# Sheet1.net
KiCad netlist of a schematic drawn in Altium Designer
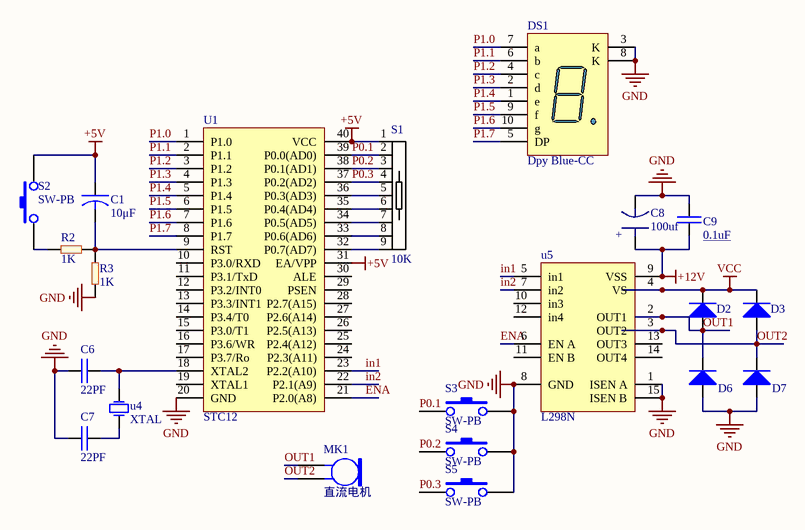
[diagram p0: Sheet1.SchDoc]

(export (version "E")
  (design (tool "Eeschema 10.0.6"))
  (components
    (comp (ref "C1")
      (value "10μF")
      (footprint "电解电容")
      (description "Capacitor")
      (libsource (lib "考核") (part "CAPACITOR"))
    )
    (comp (ref "C6") (value "22PF") (footprint "瓷片电容") (libsource (lib "考核") (part "瓷片电容")))
    (comp (ref "C7") (value "22PF") (footprint "瓷片电容") (libsource (lib "考核") (part "瓷片电容")))
    (comp (ref "C8") (value "100uf") (footprint "电解电容") (libsource (lib "考核") (part "电解电容")))
    (comp (ref "C9") (value "0.1uF") (footprint "瓷片电容") (libsource (lib "考核") (part "瓷片电容_1")))
    (comp (ref "D2")
      (value "1N4007")
      (footprint "二极管 直插")
      (fields (field (name "PUBLISHER") "Altium Limited"))
      (libsource (lib "考核") (part "1N4007"))
    )
    (comp (ref "D3")
      (value "1N4007")
      (footprint "二极管 直插")
      (fields (field (name "PUBLISHER") "Altium Limited"))
      (libsource (lib "考核") (part "1N4007"))
    )
    (comp (ref "D6")
      (value "1N4007")
      (footprint "二极管 直插")
      (fields (field (name "PUBLISHER") "Altium Limited"))
      (libsource (lib "考核") (part "1N4007"))
    )
    (comp (ref "D7")
      (value "1N4007")
      (footprint "二极管 直插")
      (fields (field (name "PUBLISHER") "Altium Limited"))
      (libsource (lib "考核") (part "1N4007"))
    )
    (comp (ref "DS1")
      (value "Dpy Blue-CC")
      (footprint "LEDDIP-10/C15.24RHD")
      (description "14.2 mm General Purpose Blue 7-Segment Display: CC, RH DP, Gray Surface")
      (fields (field (name "PUBLISHER") "Altium Limited"))
      (libsource (lib "考核") (part "Dpy Blue-CC"))
    )
    (comp (ref "MK1")
      (value "直流电机")
      (footprint "PIN2")
      (description "Microphone")
      (fields (field (name "PUBLISHER") "Altium Limited"))
      (libsource (lib "考核") (part "Mic2"))
    )
    (comp (ref "R2") (value "1K") (footprint "电阻") (libsource (lib "") (part "R_1")))
    (comp (ref "R3") (value "1K") (footprint "电阻") (libsource (lib "考核") (part "R")))
    (comp (ref "S1") (value "10K") (footprint "SIP9") (libsource (lib "考核") (part "RES-9")))
    (comp (ref "S2") (value "SW-PB") (footprint "ANJIAN") (libsource (lib "考核") (part "SW-PB")))
    (comp (ref "S3") (value "SW-PB") (footprint "ANJIAN") (libsource (lib "考核") (part "SW-PB")))
    (comp (ref "S4") (value "SW-PB") (footprint "ANJIAN") (libsource (lib "考核") (part "SW-PB")))
    (comp (ref "S5") (value "SW-PB") (footprint "ANJIAN") (libsource (lib "考核") (part "SW-PB")))
    (comp (ref "U1") (value "STC12") (footprint "STC52") (libsource (lib "考核") (part "12单片机")))
    (comp (ref "u4") (value "XTAL") (footprint "晶振.") (libsource (lib "考核") (part "XTAL")))
    (comp (ref "u5") (value "L298N") (footprint "L298N") (libsource (lib "考核") (part "L298N")))
  )
  (nets
    (net (code "1") (name "+5V") (class "Default")
      (node (ref "C1") (pin "1") (pinfunction "1_1") (pintype "passive"))
      (node (ref "S1") (pin "1") (pinfunction "1_1") (pintype "open_collector"))
      (node (ref "S2") (pin "2") (pinfunction "2_2") (pintype "passive"))
      (node (ref "U1") (pin "31") (pinfunction "EA/VPP_31") (pintype "passive"))
      (node (ref "U1") (pin "40") (pinfunction "VCC_40") (pintype "passive"))
    )
    (net (code "2") (name "+12V") (class "Default")
      (node (ref "C8") (pin "1") (pinfunction "1_1") (pintype "passive"))
      (node (ref "C9") (pin "1") (pinfunction "1_1") (pintype "passive"))
      (node (ref "u5") (pin "9") (pinfunction "VSS_9") (pintype "passive"))
    )
    (net (code "3") (name "/ENA") (class "Default")
      (node (ref "U1") (pin "21") (pinfunction "P2.0(A8)_21") (pintype "passive"))
      (node (ref "u5") (pin "6") (pinfunction "EN_A_6") (pintype "passive"))
    )
    (net (code "4") (name "/OUT1") (class "Default")
      (node (ref "D2") (pin "1") (pinfunction "1_1") (pintype "passive"))
      (node (ref "D6") (pin "2") (pinfunction "2_2") (pintype "passive"))
      (node (ref "MK1") (pin "1") (pinfunction "1_1") (pintype "passive"))
      (node (ref "u5") (pin "2") (pinfunction "OUT1_2") (pintype "passive"))
    )
    (net (code "5") (name "/OUT2") (class "Default")
      (node (ref "D3") (pin "1") (pinfunction "1_1") (pintype "passive"))
      (node (ref "D7") (pin "2") (pinfunction "2_2") (pintype "passive"))
      (node (ref "MK1") (pin "2") (pinfunction "2_2") (pintype "passive"))
      (node (ref "u5") (pin "3") (pinfunction "OUT2_3") (pintype "passive"))
    )
    (net (code "6") (name "/P0.1") (class "Default")
      (node (ref "S1") (pin "2") (pinfunction "2_2") (pintype "open_collector"))
      (node (ref "S3") (pin "1") (pinfunction "1_1") (pintype "passive"))
      (node (ref "U1") (pin "39") (pinfunction "P0.0(AD0)_39") (pintype "passive"))
    )
    (net (code "7") (name "/P0.2") (class "Default")
      (node (ref "S1") (pin "3") (pinfunction "3_3") (pintype "open_collector"))
      (node (ref "S4") (pin "1") (pinfunction "1_1") (pintype "passive"))
      (node (ref "U1") (pin "38") (pinfunction "P0.1(AD1)_38") (pintype "passive"))
    )
    (net (code "8") (name "/P0.3") (class "Default")
      (node (ref "S1") (pin "4") (pinfunction "4_4") (pintype "open_collector"))
      (node (ref "S5") (pin "1") (pinfunction "1_1") (pintype "passive"))
      (node (ref "U1") (pin "37") (pinfunction "P0.2(AD2)_37") (pintype "passive"))
    )
    (net (code "9") (name "/P1.0") (class "Default")
      (node (ref "DS1") (pin "7") (pinfunction "a_7") (pintype "passive"))
      (node (ref "U1") (pin "1") (pinfunction "P1.0_1") (pintype "passive"))
    )
    (net (code "10") (name "/P1.1") (class "Default")
      (node (ref "DS1") (pin "6") (pinfunction "b_6") (pintype "passive"))
      (node (ref "U1") (pin "2") (pinfunction "P1.1_2") (pintype "passive"))
    )
    (net (code "11") (name "/P1.2") (class "Default")
      (node (ref "DS1") (pin "4") (pinfunction "c_4") (pintype "passive"))
      (node (ref "U1") (pin "3") (pinfunction "P1.2_3") (pintype "passive"))
    )
    (net (code "12") (name "/P1.3") (class "Default")
      (node (ref "DS1") (pin "2") (pinfunction "d_2") (pintype "passive"))
      (node (ref "U1") (pin "4") (pinfunction "P1.3_4") (pintype "passive"))
    )
    (net (code "13") (name "/P1.4") (class "Default")
      (node (ref "DS1") (pin "1") (pinfunction "e_1") (pintype "passive"))
      (node (ref "U1") (pin "5") (pinfunction "P1.4_5") (pintype "passive"))
    )
    (net (code "14") (name "/P1.5") (class "Default")
      (node (ref "DS1") (pin "9") (pinfunction "f_9") (pintype "passive"))
      (node (ref "U1") (pin "6") (pinfunction "P1.5_6") (pintype "passive"))
    )
    (net (code "15") (name "/P1.6") (class "Default")
      (node (ref "DS1") (pin "10") (pinfunction "g_10") (pintype "passive"))
      (node (ref "U1") (pin "7") (pinfunction "P1.6_7") (pintype "passive"))
    )
    (net (code "16") (name "/P1.7") (class "Default")
      (node (ref "DS1") (pin "5") (pinfunction "DP_5") (pintype "passive"))
      (node (ref "U1") (pin "8") (pinfunction "P1.7_8") (pintype "passive"))
    )
    (net (code "17") (name "/in1") (class "Default")
      (node (ref "U1") (pin "23") (pinfunction "P2.2(A10)_23") (pintype "passive"))
      (node (ref "u5") (pin "5") (pinfunction "in1_5") (pintype "passive"))
    )
    (net (code "18") (name "/in2") (class "Default")
      (node (ref "U1") (pin "22") (pinfunction "P2.1(A9)_22") (pintype "passive"))
      (node (ref "u5") (pin "7") (pinfunction "in2_7") (pintype "passive"))
    )
    (net (code "19") (name "GND") (class "Default")
      (node (ref "C6") (pin "1") (pinfunction "1_1") (pintype "passive"))
      (node (ref "C7") (pin "1") (pinfunction "1_1") (pintype "passive"))
      (node (ref "C8") (pin "2") (pinfunction "2_2") (pintype "passive"))
      (node (ref "C9") (pin "2") (pinfunction "2_2") (pintype "passive"))
      (node (ref "D6") (pin "1") (pinfunction "1_1") (pintype "passive"))
      (node (ref "D7") (pin "1") (pinfunction "1_1") (pintype "passive"))
      (node (ref "DS1") (pin "3") (pinfunction "K_3") (pintype "passive"))
      (node (ref "DS1") (pin "8") (pinfunction "K_8") (pintype "passive"))
      (node (ref "R3") (pin "1") (pinfunction "1_1") (pintype "passive"))
      (node (ref "S3") (pin "2") (pinfunction "2_2") (pintype "passive"))
      (node (ref "S4") (pin "2") (pinfunction "2_2") (pintype "passive"))
      (node (ref "S5") (pin "2") (pinfunction "2_2") (pintype "passive"))
      (node (ref "U1") (pin "20") (pinfunction "GND_20") (pintype "passive"))
      (node (ref "u5") (pin "1") (pinfunction "ISEN_A_1") (pintype "passive"))
      (node (ref "u5") (pin "15") (pinfunction "ISEN_B_15") (pintype "passive"))
      (node (ref "u5") (pin "8") (pinfunction "GND_8") (pintype "passive"))
    )
    (net (code "20") (name "Net-(R2-Pad1)") (class "Default")
      (node (ref "R2") (pin "1") (pinfunction "1_1") (pintype "passive"))
      (node (ref "S2") (pin "1") (pinfunction "1_1") (pintype "passive"))
    )
    (net (code "21") (name "Net-(U1-P0.3(AD3))") (class "Default")
      (node (ref "S1") (pin "5") (pinfunction "5_5") (pintype "open_collector"))
      (node (ref "U1") (pin "36") (pinfunction "P0.3(AD3)_36") (pintype "passive"))
    )
    (net (code "22") (name "Net-(U1-P0.4(AD4))") (class "Default")
      (node (ref "S1") (pin "6") (pinfunction "6_6") (pintype "open_collector"))
      (node (ref "U1") (pin "35") (pinfunction "P0.4(AD4)_35") (pintype "passive"))
    )
    (net (code "23") (name "Net-(U1-P0.5(AD5))") (class "Default")
      (node (ref "S1") (pin "7") (pinfunction "7_7") (pintype "open_collector"))
      (node (ref "U1") (pin "34") (pinfunction "P0.5(AD5)_34") (pintype "passive"))
    )
    (net (code "24") (name "Net-(U1-P0.6(AD6))") (class "Default")
      (node (ref "S1") (pin "8") (pinfunction "8_8") (pintype "open_collector"))
      (node (ref "U1") (pin "33") (pinfunction "P0.6(AD6)_33") (pintype "passive"))
    )
    (net (code "25") (name "Net-(U1-P0.7(AD7))") (class "Default")
      (node (ref "S1") (pin "9") (pinfunction "9_9") (pintype "open_collector"))
      (node (ref "U1") (pin "32") (pinfunction "P0.7(AD7)_32") (pintype "passive"))
    )
    (net (code "26") (name "Net-(U1-RST)") (class "Default")
      (node (ref "C1") (pin "2") (pinfunction "2_2") (pintype "passive"))
      (node (ref "R2") (pin "2") (pinfunction "2_2") (pintype "passive"))
      (node (ref "R3") (pin "2") (pinfunction "2_2") (pintype "passive"))
      (node (ref "U1") (pin "9") (pinfunction "RST_9") (pintype "passive"))
    )
    (net (code "27") (name "Net-(U1-XTAL2)") (class "Default")
      (node (ref "C6") (pin "2") (pinfunction "2_2") (pintype "passive"))
      (node (ref "U1") (pin "18") (pinfunction "XTAL2_18") (pintype "passive"))
      (node (ref "u4") (pin "2") (pinfunction "OSC2_2") (pintype "passive"))
    )
    (net (code "28") (name "Net-(u4-OSC1)") (class "Default")
      (node (ref "C7") (pin "2") (pinfunction "2_2") (pintype "passive"))
      (node (ref "u4") (pin "1") (pinfunction "OSC1_1") (pintype "passive"))
    )
    (net (code "29") (name "VCC") (class "Default")
      (node (ref "D2") (pin "2") (pinfunction "2_2") (pintype "passive"))
      (node (ref "D3") (pin "2") (pinfunction "2_2") (pintype "passive"))
      (node (ref "u5") (pin "4") (pinfunction "VS_4") (pintype "passive"))
    )
    (net (code "30") (name "unconnected-(U1-ALE-Pad30)") (class "Default")
      (node (ref "U1") (pin "30") (pinfunction "ALE_30") (pintype "passive"))
    )
    (net (code "31") (name "unconnected-(U1-P2.3(A11)-Pad24)") (class "Default")
      (node (ref "U1") (pin "24") (pinfunction "P2.3(A11)_24") (pintype "passive"))
    )
    (net (code "32") (name "unconnected-(U1-P2.4(A12)-Pad25)") (class "Default")
      (node (ref "U1") (pin "25") (pinfunction "P2.4(A12)_25") (pintype "passive"))
    )
    (net (code "33") (name "unconnected-(U1-P2.5(A13)-Pad26)") (class "Default")
      (node (ref "U1") (pin "26") (pinfunction "P2.5(A13)_26") (pintype "passive"))
    )
    (net (code "34") (name "unconnected-(U1-P2.6(A14)-Pad27)") (class "Default")
      (node (ref "U1") (pin "27") (pinfunction "P2.6(A14)_27") (pintype "passive"))
    )
    (net (code "35") (name "unconnected-(U1-P2.7(A15)-Pad28)") (class "Default")
      (node (ref "U1") (pin "28") (pinfunction "P2.7(A15)_28") (pintype "passive"))
    )
    (net (code "36") (name "unconnected-(U1-P3.0{slash}RXD-Pad10)") (class "Default")
      (node (ref "U1") (pin "10") (pinfunction "P3.0/RXD_10") (pintype "passive"))
    )
    (net (code "37") (name "unconnected-(U1-P3.0{slash}T1-Pad15)") (class "Default")
      (node (ref "U1") (pin "15") (pinfunction "P3.0/T1_15") (pintype "passive"))
    )
    (net (code "38") (name "unconnected-(U1-P3.1{slash}TxD-Pad11)") (class "Default")
      (node (ref "U1") (pin "11") (pinfunction "P3.1/TxD_11") (pintype "passive"))
    )
    (net (code "39") (name "unconnected-(U1-P3.2{slash}INT0-Pad12)") (class "Default")
      (node (ref "U1") (pin "12") (pinfunction "P3.2/INT0_12") (pintype "passive"))
    )
    (net (code "40") (name "unconnected-(U1-P3.3{slash}INT1-Pad13)") (class "Default")
      (node (ref "U1") (pin "13") (pinfunction "P3.3/INT1_13") (pintype "passive"))
    )
    (net (code "41") (name "unconnected-(U1-P3.4{slash}T0-Pad14)") (class "Default")
      (node (ref "U1") (pin "14") (pinfunction "P3.4/T0_14") (pintype "passive"))
    )
    (net (code "42") (name "unconnected-(U1-P3.6{slash}WR-Pad16)") (class "Default")
      (node (ref "U1") (pin "16") (pinfunction "P3.6/WR_16") (pintype "passive"))
    )
    (net (code "43") (name "unconnected-(U1-P3.7{slash}Ro-Pad17)") (class "Default")
      (node (ref "U1") (pin "17") (pinfunction "P3.7/Ro_17") (pintype "passive"))
    )
    (net (code "44") (name "unconnected-(U1-PSEN-Pad29)") (class "Default")
      (node (ref "U1") (pin "29") (pinfunction "PSEN_29") (pintype "passive"))
    )
    (net (code "45") (name "unconnected-(U1-XTAL1-Pad19)") (class "Default")
      (node (ref "U1") (pin "19") (pinfunction "XTAL1_19") (pintype "passive"))
    )
    (net (code "46") (name "unconnected-(u5-EN_B-Pad11)") (class "Default")
      (node (ref "u5") (pin "11") (pinfunction "EN_B_11") (pintype "passive"))
    )
    (net (code "47") (name "unconnected-(u5-OUT3-Pad13)") (class "Default")
      (node (ref "u5") (pin "13") (pinfunction "OUT3_13") (pintype "passive"))
    )
    (net (code "48") (name "unconnected-(u5-OUT4-Pad14)") (class "Default")
      (node (ref "u5") (pin "14") (pinfunction "OUT4_14") (pintype "passive"))
    )
    (net (code "49") (name "unconnected-(u5-in3-Pad10)") (class "Default")
      (node (ref "u5") (pin "10") (pinfunction "in3_10") (pintype "passive"))
    )
    (net (code "50") (name "unconnected-(u5-in4-Pad12)") (class "Default")
      (node (ref "u5") (pin "12") (pinfunction "in4_12") (pintype "passive"))
    )
  )
)
